# design.net
KiCad netlist of a schematic drawn in Altium Designer
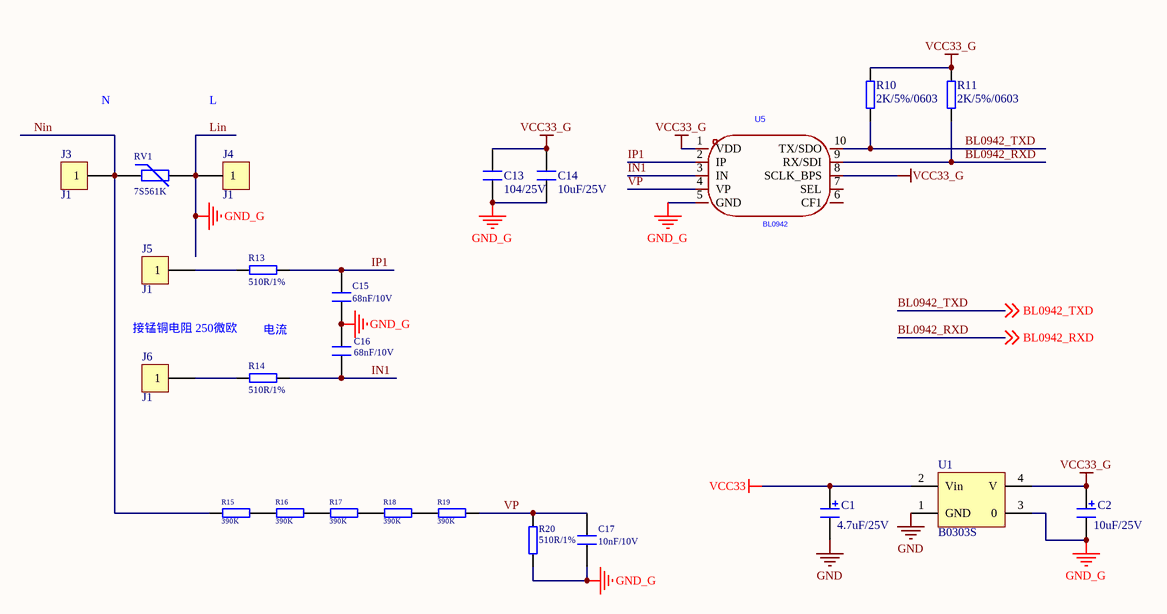
[diagram p0: 计量.SchDoc]

(export (version "E")
  (design (tool "Eeschema 10.0.6"))
  (components
    (comp (ref "C1") (value "4.7uF/25V") (footprint "0805R") (libsource (lib "ES_Schematic") (part "CAP+")))
    (comp (ref "C2") (value "10uF/25V") (footprint "0805R") (libsource (lib "ES_Schematic") (part "CAP+")))
    (comp (ref "C13") (value "104/25V") (footprint "0603R") (libsource (lib "ES_Schematic") (part "CAP_1")))
    (comp (ref "C14") (value "10uF/25V") (footprint "0603R") (libsource (lib "ES_Schematic") (part "CAP_1")))
    (comp (ref "C15") (value "68nF/10V") (footprint "0603R") (libsource (lib "ES_Schematic") (part "CAP")))
    (comp (ref "C16") (value "68nF/10V") (footprint "0603R") (libsource (lib "ES_Schematic") (part "CAP")))
    (comp (ref "C17") (value "10nF/10V") (footprint "0603R") (libsource (lib "ES_Schematic") (part "CAP")))
    (comp (ref "J3") (value "J1") (footprint "贴片焊盘V1（3*2椭圆）") (libsource (lib "ES_Schematic") (part "J1")))
    (comp (ref "J4") (value "J1") (footprint "贴片焊盘V1（3*2椭圆）") (libsource (lib "") (part "J1_1")))
    (comp (ref "J5") (value "J1") (footprint "贴片焊盘V1（3*2椭圆）") (libsource (lib "ES_Schematic") (part "J1")))
    (comp (ref "J6") (value "J1") (footprint "贴片焊盘V1（3*2椭圆）") (libsource (lib "ES_Schematic") (part "J1")))
    (comp (ref "R10") (value "2K/5%/0603") (footprint "0603R") (libsource (lib "ES_Schematic") (part "RES")))
    (comp (ref "R11") (value "2K/5%/0603") (footprint "0603R") (libsource (lib "ES_Schematic") (part "RES")))
    (comp (ref "R13") (value "510R/1%") (footprint "0603R") (libsource (lib "ES_Schematic") (part "RES")))
    (comp (ref "R14") (value "510R/1%") (footprint "0603R") (libsource (lib "ES_Schematic") (part "RES")))
    (comp (ref "R15") (value "390K") (footprint "0805R") (libsource (lib "ES_Schematic") (part "RES")))
    (comp (ref "R16") (value "390K") (footprint "0805R") (libsource (lib "ES_Schematic") (part "RES")))
    (comp (ref "R17") (value "390K") (footprint "0805R") (libsource (lib "ES_Schematic") (part "RES")))
    (comp (ref "R18") (value "390K") (footprint "0805R") (libsource (lib "ES_Schematic") (part "RES")))
    (comp (ref "R19") (value "390K") (footprint "0805R") (libsource (lib "ES_Schematic") (part "RES")))
    (comp (ref "R20") (value "510R/1%") (footprint "0603R") (libsource (lib "ES_Schematic") (part "RES")))
    (comp (ref "RV1")
      (value "7S561K")
      (footprint "10D821K")
      (description "Varistor (Voltage-Sensitive Resistor)")
      (fields (field (name "PUBLISHER") "Altium Limited"))
      (libsource (lib "Miscellaneous Devices") (part "Res Varistor"))
    )
    (comp (ref "U1") (value "B0303S") (footprint "B1205S-1WR3") (libsource (lib "sangjian") (part "B0505S")))
    (comp (ref "U5")
      (value "BL0942")
      (footprint "BL0942-10pin")
      (fields (field (name "MANUFACTURER") "BL(上海贝岭)"))
      (libsource (lib "altium-import") (part "root_0_BL0942_C2837510_"))
    )
  )
  (nets
    (net (code "1") (name "/IN1") (class "Default")
      (node (ref "C16") (pin "1") (pinfunction "1_1") (pintype "passive"))
      (node (ref "R14") (pin "2") (pinfunction "2_2") (pintype "passive"))
      (node (ref "U5") (pin "3") (pinfunction "IN_3") (pintype "passive"))
    )
    (net (code "2") (name "/IP1") (class "Default")
      (node (ref "C15") (pin "1") (pinfunction "1_1") (pintype "passive"))
      (node (ref "R13") (pin "2") (pinfunction "2_2") (pintype "passive"))
      (node (ref "U5") (pin "2") (pinfunction "IP_2") (pintype "passive"))
    )
    (net (code "3") (name "/Nin") (class "Default")
      (node (ref "J3") (pin "1") (pinfunction "1_1") (pintype "passive"))
      (node (ref "R15") (pin "2") (pinfunction "2_2") (pintype "passive"))
      (node (ref "RV1") (pin "1") (pinfunction "1_1") (pintype "passive"))
    )
    (net (code "4") (name "/VP") (class "Default")
      (node (ref "C17") (pin "1") (pinfunction "1_1") (pintype "passive"))
      (node (ref "R19") (pin "1") (pinfunction "1_1") (pintype "passive"))
      (node (ref "R20") (pin "2") (pinfunction "2_2") (pintype "passive"))
      (node (ref "U5") (pin "4") (pinfunction "VP_4") (pintype "passive"))
    )
    (net (code "5") (name "BL0942_RXD") (class "Default")
      (node (ref "R11") (pin "1") (pinfunction "1_1") (pintype "passive"))
      (node (ref "U5") (pin "9") (pinfunction "RX/SDI_9") (pintype "passive"))
    )
    (net (code "6") (name "BL0942_TXD") (class "Default")
      (node (ref "R10") (pin "1") (pinfunction "1_1") (pintype "passive"))
      (node (ref "U5") (pin "10") (pinfunction "TX/SDO_10") (pintype "passive"))
    )
    (net (code "7") (name "GND") (class "Default")
      (node (ref "C1") (pin "2") (pinfunction "2_2") (pintype "passive"))
      (node (ref "U1") (pin "1") (pinfunction "GND_1") (pintype "passive"))
    )
    (net (code "8") (name "GND_G") (class "Default")
      (node (ref "C13") (pin "1") (pinfunction "1_1") (pintype "passive"))
      (node (ref "C14") (pin "1") (pinfunction "1_1") (pintype "passive"))
      (node (ref "C15") (pin "2") (pinfunction "2_2") (pintype "passive"))
      (node (ref "C16") (pin "2") (pinfunction "2_2") (pintype "passive"))
      (node (ref "C17") (pin "2") (pinfunction "2_2") (pintype "passive"))
      (node (ref "C2") (pin "2") (pinfunction "2_2") (pintype "passive"))
      (node (ref "J4") (pin "1") (pinfunction "1_1") (pintype "passive"))
      (node (ref "R20") (pin "1") (pinfunction "1_1") (pintype "passive"))
      (node (ref "RV1") (pin "2") (pinfunction "2_2") (pintype "passive"))
      (node (ref "U1") (pin "3") (pinfunction "0_3") (pintype "passive"))
      (node (ref "U5") (pin "5") (pinfunction "GND_5") (pintype "passive"))
    )
    (net (code "9") (name "Net-(J5-Pad1)") (class "Default")
      (node (ref "J5") (pin "1") (pinfunction "1_1") (pintype "passive"))
      (node (ref "R13") (pin "1") (pinfunction "1_1") (pintype "passive"))
    )
    (net (code "10") (name "Net-(J6-Pad1)") (class "Default")
      (node (ref "J6") (pin "1") (pinfunction "1_1") (pintype "passive"))
      (node (ref "R14") (pin "1") (pinfunction "1_1") (pintype "passive"))
    )
    (net (code "11") (name "Net-(R15-Pad1)") (class "Default")
      (node (ref "R15") (pin "1") (pinfunction "1_1") (pintype "passive"))
      (node (ref "R16") (pin "2") (pinfunction "2_2") (pintype "passive"))
    )
    (net (code "12") (name "Net-(R16-Pad1)") (class "Default")
      (node (ref "R16") (pin "1") (pinfunction "1_1") (pintype "passive"))
      (node (ref "R17") (pin "2") (pinfunction "2_2") (pintype "passive"))
    )
    (net (code "13") (name "Net-(R17-Pad1)") (class "Default")
      (node (ref "R17") (pin "1") (pinfunction "1_1") (pintype "passive"))
      (node (ref "R18") (pin "2") (pinfunction "2_2") (pintype "passive"))
    )
    (net (code "14") (name "Net-(R18-Pad1)") (class "Default")
      (node (ref "R18") (pin "1") (pinfunction "1_1") (pintype "passive"))
      (node (ref "R19") (pin "2") (pinfunction "2_2") (pintype "passive"))
    )
    (net (code "15") (name "VCC33") (class "Default")
      (node (ref "C1") (pin "1") (pinfunction "1_1") (pintype "passive"))
      (node (ref "U1") (pin "2") (pinfunction "Vin_2") (pintype "passive"))
    )
    (net (code "16") (name "VCC33_G") (class "Default")
      (node (ref "C13") (pin "2") (pinfunction "2_2") (pintype "passive"))
      (node (ref "C14") (pin "2") (pinfunction "2_2") (pintype "passive"))
      (node (ref "C2") (pin "1") (pinfunction "1_1") (pintype "passive"))
      (node (ref "R10") (pin "2") (pinfunction "2_2") (pintype "passive"))
      (node (ref "R11") (pin "2") (pinfunction "2_2") (pintype "passive"))
      (node (ref "U1") (pin "4") (pinfunction "V_4") (pintype "passive"))
      (node (ref "U5") (pin "1") (pinfunction "VDD_1") (pintype "passive"))
      (node (ref "U5") (pin "8") (pinfunction "SCLK_BPS_8") (pintype "passive"))
    )
    (net (code "17") (name "unconnected-(U5-CF1-Pad6)") (class "Default")
      (node (ref "U5") (pin "6") (pinfunction "CF1_6") (pintype "passive"))
    )
    (net (code "18") (name "unconnected-(U5-SEL-Pad7)") (class "Default")
      (node (ref "U5") (pin "7") (pinfunction "SEL_7") (pintype "passive"))
    )
  )
)
